# Glasses-LensBoard.net
KiCad netlist of a schematic drawn in Altium Designer
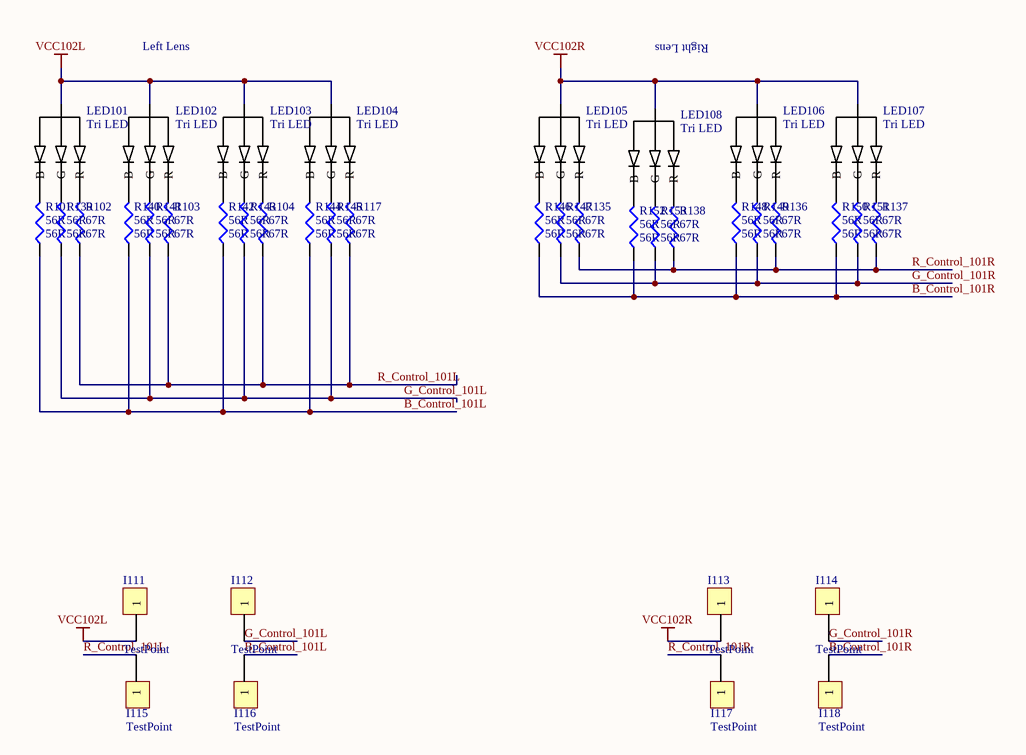
[diagram p0: Glasses-LensBoard.SchDoc]

(export (version "E")
  (design (tool "Eeschema 10.0.6"))
  (components
    (comp (ref "I111") (value "TestPoint") (footprint "TestPoint") (libsource (lib "") (part "TestPoint_1")))
    (comp (ref "I112") (value "TestPoint") (footprint "TestPoint") (libsource (lib "") (part "TestPoint_1")))
    (comp (ref "I113") (value "TestPoint") (footprint "TestPoint") (libsource (lib "") (part "TestPoint_1")))
    (comp (ref "I114") (value "TestPoint") (footprint "TestPoint") (libsource (lib "") (part "TestPoint_1")))
    (comp (ref "I115")
      (value "TestPoint")
      (footprint "TestPoint")
      (libsource (lib "Schlib1") (part "TestPoint"))
    )
    (comp (ref "I116")
      (value "TestPoint")
      (footprint "TestPoint")
      (libsource (lib "Schlib1") (part "TestPoint"))
    )
    (comp (ref "I117")
      (value "TestPoint")
      (footprint "TestPoint")
      (libsource (lib "Schlib1") (part "TestPoint"))
    )
    (comp (ref "I118")
      (value "TestPoint")
      (footprint "TestPoint")
      (libsource (lib "Schlib1") (part "TestPoint"))
    )
    (comp (ref "LED101")
      (value "Tri LED")
      (footprint "CLV1A-FKB")
      (libsource (lib "Schlib1") (part "Tri LED"))
    )
    (comp (ref "LED102")
      (value "Tri LED")
      (footprint "CLV1A-FKB")
      (libsource (lib "Schlib1") (part "Tri LED"))
    )
    (comp (ref "LED103")
      (value "Tri LED")
      (footprint "CLV1A-FKB")
      (libsource (lib "Schlib1") (part "Tri LED"))
    )
    (comp (ref "LED104")
      (value "Tri LED")
      (footprint "CLV1A-FKB")
      (libsource (lib "Schlib1") (part "Tri LED"))
    )
    (comp (ref "LED105")
      (value "Tri LED")
      (footprint "CLV1A-FKB")
      (libsource (lib "Schlib1") (part "Tri LED"))
    )
    (comp (ref "LED106")
      (value "Tri LED")
      (footprint "CLV1A-FKB")
      (libsource (lib "Schlib1") (part "Tri LED"))
    )
    (comp (ref "LED107")
      (value "Tri LED")
      (footprint "CLV1A-FKB")
      (libsource (lib "Schlib1") (part "Tri LED"))
    )
    (comp (ref "LED108")
      (value "Tri LED")
      (footprint "CLV1A-FKB")
      (libsource (lib "Schlib1") (part "Tri LED"))
    )
    (comp (ref "R101")
      (value "56R")
      (footprint "0603")
      (description "Resistor")
      (fields (field (name "ALTIUM_VALUE") "56R") (field (name "PUBLISHER") "Altium Limited"))
      (libsource (lib "Miscellaneous Devices") (part "Res3"))
    )
    (comp (ref "R102")
      (value "67R")
      (footprint "0603")
      (description "Resistor")
      (fields (field (name "ALTIUM_VALUE") "67R") (field (name "PUBLISHER") "Altium Limited"))
      (libsource (lib "Miscellaneous Devices") (part "Res3"))
    )
    (comp (ref "R103")
      (value "67R")
      (footprint "0603")
      (description "Resistor")
      (fields (field (name "ALTIUM_VALUE") "67R") (field (name "PUBLISHER") "Altium Limited"))
      (libsource (lib "Miscellaneous Devices") (part "Res3"))
    )
    (comp (ref "R104")
      (value "67R")
      (footprint "0603")
      (description "Resistor")
      (fields (field (name "ALTIUM_VALUE") "67R") (field (name "PUBLISHER") "Altium Limited"))
      (libsource (lib "Miscellaneous Devices") (part "Res3"))
    )
    (comp (ref "R117")
      (value "67R")
      (footprint "0603")
      (description "Resistor")
      (fields (field (name "ALTIUM_VALUE") "67R") (field (name "PUBLISHER") "Altium Limited"))
      (libsource (lib "Miscellaneous Devices") (part "Res3"))
    )
    (comp (ref "R135")
      (value "67R")
      (footprint "0603")
      (description "Resistor")
      (fields (field (name "ALTIUM_VALUE") "67R") (field (name "PUBLISHER") "Altium Limited"))
      (libsource (lib "Miscellaneous Devices") (part "Res3"))
    )
    (comp (ref "R136")
      (value "67R")
      (footprint "0603")
      (description "Resistor")
      (fields (field (name "ALTIUM_VALUE") "67R") (field (name "PUBLISHER") "Altium Limited"))
      (libsource (lib "Miscellaneous Devices") (part "Res3"))
    )
    (comp (ref "R137")
      (value "67R")
      (footprint "0603")
      (description "Resistor")
      (fields (field (name "ALTIUM_VALUE") "67R") (field (name "PUBLISHER") "Altium Limited"))
      (libsource (lib "Miscellaneous Devices") (part "Res3"))
    )
    (comp (ref "R138")
      (value "67R")
      (footprint "0603")
      (description "Resistor")
      (fields (field (name "ALTIUM_VALUE") "67R") (field (name "PUBLISHER") "Altium Limited"))
      (libsource (lib "Miscellaneous Devices") (part "Res3"))
    )
    (comp (ref "R139")
      (value "56R")
      (footprint "0603")
      (description "Resistor")
      (fields (field (name "ALTIUM_VALUE") "56R") (field (name "PUBLISHER") "Altium Limited"))
      (libsource (lib "Miscellaneous Devices") (part "Res3"))
    )
    (comp (ref "R140")
      (value "56R")
      (footprint "0603")
      (description "Resistor")
      (fields (field (name "ALTIUM_VALUE") "56R") (field (name "PUBLISHER") "Altium Limited"))
      (libsource (lib "Miscellaneous Devices") (part "Res3"))
    )
    (comp (ref "R141")
      (value "56R")
      (footprint "0603")
      (description "Resistor")
      (fields (field (name "ALTIUM_VALUE") "56R") (field (name "PUBLISHER") "Altium Limited"))
      (libsource (lib "Miscellaneous Devices") (part "Res3"))
    )
    (comp (ref "R142")
      (value "56R")
      (footprint "0603")
      (description "Resistor")
      (fields (field (name "ALTIUM_VALUE") "56R") (field (name "PUBLISHER") "Altium Limited"))
      (libsource (lib "Miscellaneous Devices") (part "Res3"))
    )
    (comp (ref "R143")
      (value "56R")
      (footprint "0603")
      (description "Resistor")
      (fields (field (name "ALTIUM_VALUE") "56R") (field (name "PUBLISHER") "Altium Limited"))
      (libsource (lib "Miscellaneous Devices") (part "Res3"))
    )
    (comp (ref "R144")
      (value "56R")
      (footprint "0603")
      (description "Resistor")
      (fields (field (name "ALTIUM_VALUE") "56R") (field (name "PUBLISHER") "Altium Limited"))
      (libsource (lib "Miscellaneous Devices") (part "Res3"))
    )
    (comp (ref "R145")
      (value "56R")
      (footprint "0603")
      (description "Resistor")
      (fields (field (name "ALTIUM_VALUE") "56R") (field (name "PUBLISHER") "Altium Limited"))
      (libsource (lib "Miscellaneous Devices") (part "Res3"))
    )
    (comp (ref "R146")
      (value "56R")
      (footprint "0603")
      (description "Resistor")
      (fields (field (name "ALTIUM_VALUE") "56R") (field (name "PUBLISHER") "Altium Limited"))
      (libsource (lib "Miscellaneous Devices") (part "Res3"))
    )
    (comp (ref "R147")
      (value "56R")
      (footprint "0603")
      (description "Resistor")
      (fields (field (name "ALTIUM_VALUE") "56R") (field (name "PUBLISHER") "Altium Limited"))
      (libsource (lib "Miscellaneous Devices") (part "Res3"))
    )
    (comp (ref "R148")
      (value "56R")
      (footprint "0603")
      (description "Resistor")
      (fields (field (name "ALTIUM_VALUE") "56R") (field (name "PUBLISHER") "Altium Limited"))
      (libsource (lib "Miscellaneous Devices") (part "Res3"))
    )
    (comp (ref "R149")
      (value "56R")
      (footprint "0603")
      (description "Resistor")
      (fields (field (name "ALTIUM_VALUE") "56R") (field (name "PUBLISHER") "Altium Limited"))
      (libsource (lib "Miscellaneous Devices") (part "Res3"))
    )
    (comp (ref "R150")
      (value "56R")
      (footprint "0603")
      (description "Resistor")
      (fields (field (name "ALTIUM_VALUE") "56R") (field (name "PUBLISHER") "Altium Limited"))
      (libsource (lib "Miscellaneous Devices") (part "Res3"))
    )
    (comp (ref "R151")
      (value "56R")
      (footprint "0603")
      (description "Resistor")
      (fields (field (name "ALTIUM_VALUE") "56R") (field (name "PUBLISHER") "Altium Limited"))
      (libsource (lib "Miscellaneous Devices") (part "Res3"))
    )
    (comp (ref "R152")
      (value "56R")
      (footprint "0603")
      (description "Resistor")
      (fields (field (name "ALTIUM_VALUE") "56R") (field (name "PUBLISHER") "Altium Limited"))
      (libsource (lib "Miscellaneous Devices") (part "Res3"))
    )
    (comp (ref "R153")
      (value "56R")
      (footprint "0603")
      (description "Resistor")
      (fields (field (name "ALTIUM_VALUE") "56R") (field (name "PUBLISHER") "Altium Limited"))
      (libsource (lib "Miscellaneous Devices") (part "Res3"))
    )
  )
  (nets
    (net (code "1") (name "/B_Control_101L") (class "Default")
      (node (ref "I116") (pin "1") (pinfunction "1_1") (pintype "passive"))
      (node (ref "R101") (pin "1") (pinfunction "1_1") (pintype "passive"))
      (node (ref "R140") (pin "1") (pinfunction "1_1") (pintype "passive"))
      (node (ref "R142") (pin "1") (pinfunction "1_1") (pintype "passive"))
      (node (ref "R144") (pin "1") (pinfunction "1_1") (pintype "passive"))
    )
    (net (code "2") (name "/B_Control_101R") (class "Default")
      (node (ref "I118") (pin "1") (pinfunction "1_1") (pintype "passive"))
      (node (ref "R146") (pin "1") (pinfunction "1_1") (pintype "passive"))
      (node (ref "R148") (pin "1") (pinfunction "1_1") (pintype "passive"))
      (node (ref "R150") (pin "1") (pinfunction "1_1") (pintype "passive"))
      (node (ref "R152") (pin "1") (pinfunction "1_1") (pintype "passive"))
    )
    (net (code "3") (name "/G_Control_101L") (class "Default")
      (node (ref "I112") (pin "1") (pinfunction "1_1") (pintype "passive"))
      (node (ref "R139") (pin "1") (pinfunction "1_1") (pintype "passive"))
      (node (ref "R141") (pin "1") (pinfunction "1_1") (pintype "passive"))
      (node (ref "R143") (pin "1") (pinfunction "1_1") (pintype "passive"))
      (node (ref "R145") (pin "1") (pinfunction "1_1") (pintype "passive"))
    )
    (net (code "4") (name "/G_Control_101R") (class "Default")
      (node (ref "I114") (pin "1") (pinfunction "1_1") (pintype "passive"))
      (node (ref "R147") (pin "1") (pinfunction "1_1") (pintype "passive"))
      (node (ref "R149") (pin "1") (pinfunction "1_1") (pintype "passive"))
      (node (ref "R151") (pin "1") (pinfunction "1_1") (pintype "passive"))
      (node (ref "R153") (pin "1") (pinfunction "1_1") (pintype "passive"))
    )
    (net (code "5") (name "/R_Control_101L") (class "Default")
      (node (ref "I115") (pin "1") (pinfunction "1_1") (pintype "passive"))
      (node (ref "R102") (pin "1") (pinfunction "1_1") (pintype "passive"))
      (node (ref "R103") (pin "1") (pinfunction "1_1") (pintype "passive"))
      (node (ref "R104") (pin "1") (pinfunction "1_1") (pintype "passive"))
      (node (ref "R117") (pin "1") (pinfunction "1_1") (pintype "passive"))
    )
    (net (code "6") (name "/R_Control_101R") (class "Default")
      (node (ref "I117") (pin "1") (pinfunction "1_1") (pintype "passive"))
      (node (ref "R135") (pin "1") (pinfunction "1_1") (pintype "passive"))
      (node (ref "R136") (pin "1") (pinfunction "1_1") (pintype "passive"))
      (node (ref "R137") (pin "1") (pinfunction "1_1") (pintype "passive"))
      (node (ref "R138") (pin "1") (pinfunction "1_1") (pintype "passive"))
    )
    (net (code "7") (name "Net-(LED101-B)") (class "Default")
      (node (ref "LED101") (pin "3") (pinfunction "B_3") (pintype "passive"))
      (node (ref "R101") (pin "2") (pinfunction "2_2") (pintype "passive"))
    )
    (net (code "8") (name "Net-(LED101-G)") (class "Default")
      (node (ref "LED101") (pin "4") (pinfunction "G_4") (pintype "passive"))
      (node (ref "R139") (pin "2") (pinfunction "2_2") (pintype "passive"))
    )
    (net (code "9") (name "Net-(LED101-R)") (class "Default")
      (node (ref "LED101") (pin "1") (pinfunction "R_1") (pintype "passive"))
      (node (ref "R102") (pin "2") (pinfunction "2_2") (pintype "passive"))
    )
    (net (code "10") (name "Net-(LED102-B)") (class "Default")
      (node (ref "LED102") (pin "3") (pinfunction "B_3") (pintype "passive"))
      (node (ref "R140") (pin "2") (pinfunction "2_2") (pintype "passive"))
    )
    (net (code "11") (name "Net-(LED102-G)") (class "Default")
      (node (ref "LED102") (pin "4") (pinfunction "G_4") (pintype "passive"))
      (node (ref "R141") (pin "2") (pinfunction "2_2") (pintype "passive"))
    )
    (net (code "12") (name "Net-(LED102-R)") (class "Default")
      (node (ref "LED102") (pin "1") (pinfunction "R_1") (pintype "passive"))
      (node (ref "R103") (pin "2") (pinfunction "2_2") (pintype "passive"))
    )
    (net (code "13") (name "Net-(LED103-B)") (class "Default")
      (node (ref "LED103") (pin "3") (pinfunction "B_3") (pintype "passive"))
      (node (ref "R142") (pin "2") (pinfunction "2_2") (pintype "passive"))
    )
    (net (code "14") (name "Net-(LED103-G)") (class "Default")
      (node (ref "LED103") (pin "4") (pinfunction "G_4") (pintype "passive"))
      (node (ref "R143") (pin "2") (pinfunction "2_2") (pintype "passive"))
    )
    (net (code "15") (name "Net-(LED103-R)") (class "Default")
      (node (ref "LED103") (pin "1") (pinfunction "R_1") (pintype "passive"))
      (node (ref "R104") (pin "2") (pinfunction "2_2") (pintype "passive"))
    )
    (net (code "16") (name "Net-(LED104-B)") (class "Default")
      (node (ref "LED104") (pin "3") (pinfunction "B_3") (pintype "passive"))
      (node (ref "R144") (pin "2") (pinfunction "2_2") (pintype "passive"))
    )
    (net (code "17") (name "Net-(LED104-G)") (class "Default")
      (node (ref "LED104") (pin "4") (pinfunction "G_4") (pintype "passive"))
      (node (ref "R145") (pin "2") (pinfunction "2_2") (pintype "passive"))
    )
    (net (code "18") (name "Net-(LED104-R)") (class "Default")
      (node (ref "LED104") (pin "1") (pinfunction "R_1") (pintype "passive"))
      (node (ref "R117") (pin "2") (pinfunction "2_2") (pintype "passive"))
    )
    (net (code "19") (name "Net-(LED105-B)") (class "Default")
      (node (ref "LED105") (pin "3") (pinfunction "B_3") (pintype "passive"))
      (node (ref "R146") (pin "2") (pinfunction "2_2") (pintype "passive"))
    )
    (net (code "20") (name "Net-(LED105-G)") (class "Default")
      (node (ref "LED105") (pin "4") (pinfunction "G_4") (pintype "passive"))
      (node (ref "R147") (pin "2") (pinfunction "2_2") (pintype "passive"))
    )
    (net (code "21") (name "Net-(LED105-R)") (class "Default")
      (node (ref "LED105") (pin "1") (pinfunction "R_1") (pintype "passive"))
      (node (ref "R135") (pin "2") (pinfunction "2_2") (pintype "passive"))
    )
    (net (code "22") (name "Net-(LED106-B)") (class "Default")
      (node (ref "LED106") (pin "3") (pinfunction "B_3") (pintype "passive"))
      (node (ref "R148") (pin "2") (pinfunction "2_2") (pintype "passive"))
    )
    (net (code "23") (name "Net-(LED106-G)") (class "Default")
      (node (ref "LED106") (pin "4") (pinfunction "G_4") (pintype "passive"))
      (node (ref "R149") (pin "2") (pinfunction "2_2") (pintype "passive"))
    )
    (net (code "24") (name "Net-(LED106-R)") (class "Default")
      (node (ref "LED106") (pin "1") (pinfunction "R_1") (pintype "passive"))
      (node (ref "R136") (pin "2") (pinfunction "2_2") (pintype "passive"))
    )
    (net (code "25") (name "Net-(LED107-B)") (class "Default")
      (node (ref "LED107") (pin "3") (pinfunction "B_3") (pintype "passive"))
      (node (ref "R150") (pin "2") (pinfunction "2_2") (pintype "passive"))
    )
    (net (code "26") (name "Net-(LED107-G)") (class "Default")
      (node (ref "LED107") (pin "4") (pinfunction "G_4") (pintype "passive"))
      (node (ref "R151") (pin "2") (pinfunction "2_2") (pintype "passive"))
    )
    (net (code "27") (name "Net-(LED107-R)") (class "Default")
      (node (ref "LED107") (pin "1") (pinfunction "R_1") (pintype "passive"))
      (node (ref "R137") (pin "2") (pinfunction "2_2") (pintype "passive"))
    )
    (net (code "28") (name "Net-(LED108-B)") (class "Default")
      (node (ref "LED108") (pin "3") (pinfunction "B_3") (pintype "passive"))
      (node (ref "R152") (pin "2") (pinfunction "2_2") (pintype "passive"))
    )
    (net (code "29") (name "Net-(LED108-G)") (class "Default")
      (node (ref "LED108") (pin "4") (pinfunction "G_4") (pintype "passive"))
      (node (ref "R153") (pin "2") (pinfunction "2_2") (pintype "passive"))
    )
    (net (code "30") (name "Net-(LED108-R)") (class "Default")
      (node (ref "LED108") (pin "1") (pinfunction "R_1") (pintype "passive"))
      (node (ref "R138") (pin "2") (pinfunction "2_2") (pintype "passive"))
    )
    (net (code "31") (name "VCC102L") (class "Default")
      (node (ref "I111") (pin "1") (pinfunction "1_1") (pintype "passive"))
      (node (ref "LED101") (pin "2") (pinfunction "Common_2") (pintype "passive"))
      (node (ref "LED102") (pin "2") (pinfunction "Common_2") (pintype "passive"))
      (node (ref "LED103") (pin "2") (pinfunction "Common_2") (pintype "passive"))
      (node (ref "LED104") (pin "2") (pinfunction "Common_2") (pintype "passive"))
    )
    (net (code "32") (name "VCC102R") (class "Default")
      (node (ref "I113") (pin "1") (pinfunction "1_1") (pintype "passive"))
      (node (ref "LED105") (pin "2") (pinfunction "Common_2") (pintype "passive"))
      (node (ref "LED106") (pin "2") (pinfunction "Common_2") (pintype "passive"))
      (node (ref "LED107") (pin "2") (pinfunction "Common_2") (pintype "passive"))
      (node (ref "LED108") (pin "2") (pinfunction "Common_2") (pintype "passive"))
    )
  )
)
